# PiDGC.net
KiCad netlist of a schematic drawn in EAGLE
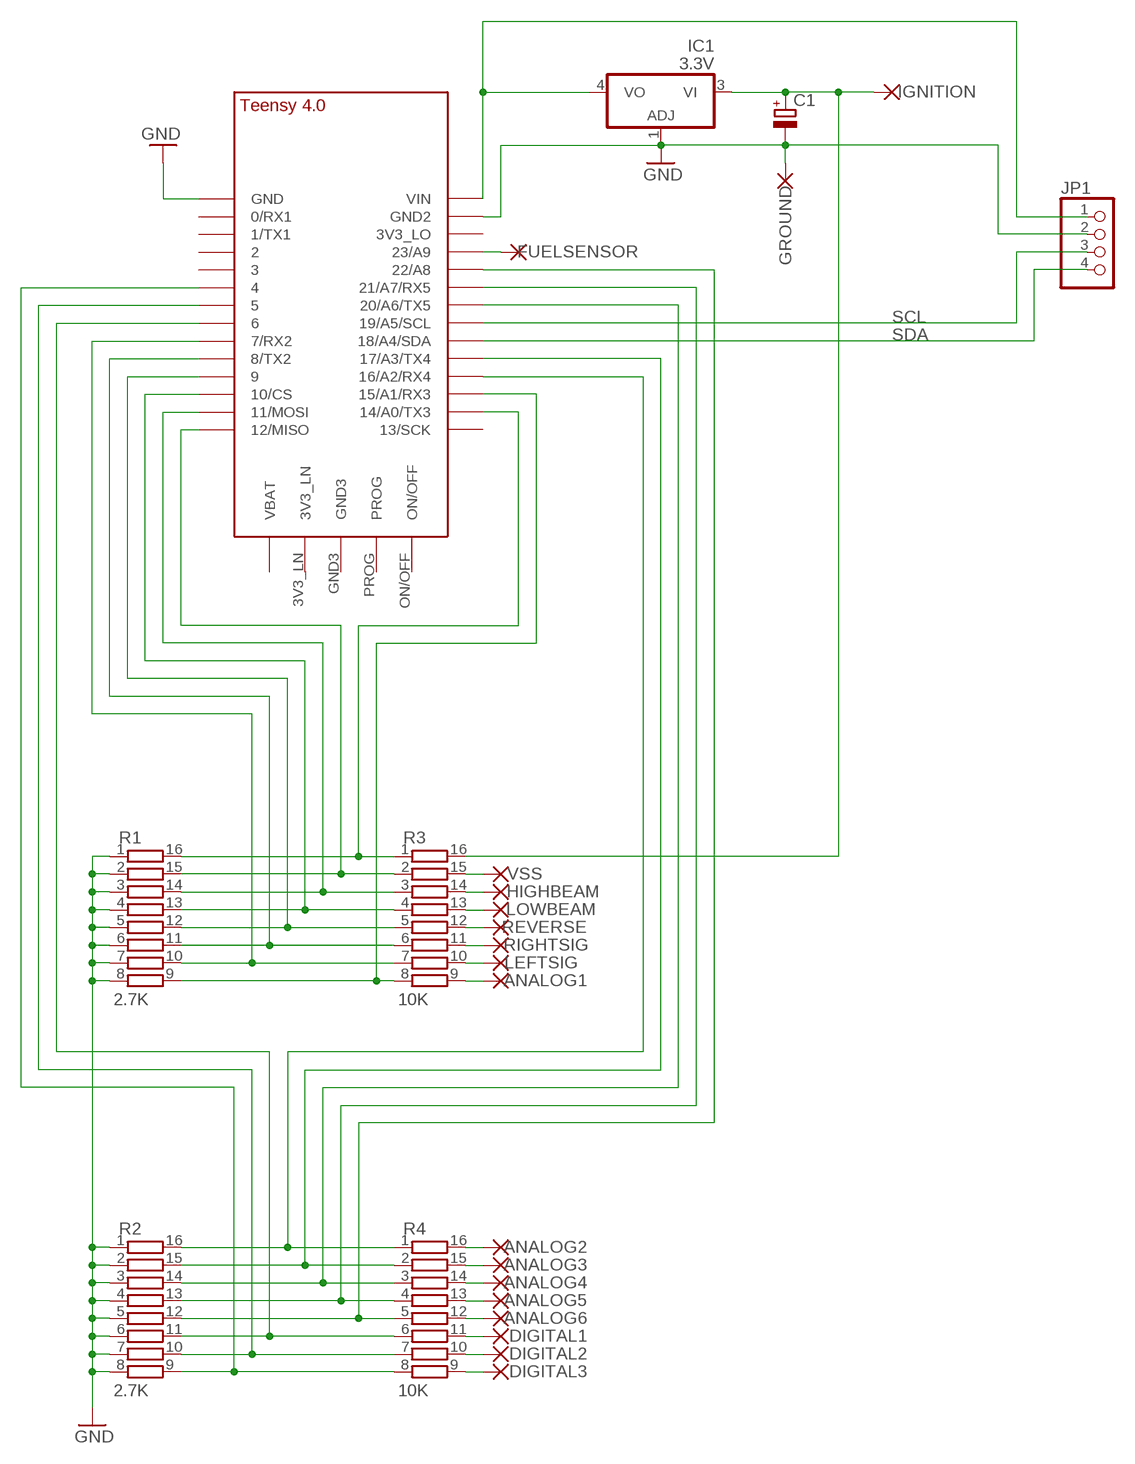
[diagram p0: schematic, sheet 1]

(export (version "E")
  (design (tool "Eeschema 10.0.6"))
  (components
    (comp (ref "ANALOG1")
      (value "WIREPAD3,81/1,4")
      (footprint "eagle-import:3,81_1,4")
      (libsource (lib "eagle-import") (part "WIREPAD3,81/1,4"))
    )
    (comp (ref "ANALOG2")
      (value "WIREPAD3,81/1,4")
      (footprint "eagle-import:3,81_1,4")
      (libsource (lib "eagle-import") (part "WIREPAD3,81/1,4"))
    )
    (comp (ref "ANALOG3")
      (value "WIREPAD3,81/1,4")
      (footprint "eagle-import:3,81_1,4")
      (libsource (lib "eagle-import") (part "WIREPAD3,81/1,4"))
    )
    (comp (ref "ANALOG4")
      (value "WIREPAD3,81/1,4")
      (footprint "eagle-import:3,81_1,4")
      (libsource (lib "eagle-import") (part "WIREPAD3,81/1,4"))
    )
    (comp (ref "ANALOG5")
      (value "WIREPAD3,81/1,4")
      (footprint "eagle-import:3,81_1,4")
      (libsource (lib "eagle-import") (part "WIREPAD3,81/1,4"))
    )
    (comp (ref "ANALOG6")
      (value "WIREPAD3,81/1,4")
      (footprint "eagle-import:3,81_1,4")
      (libsource (lib "eagle-import") (part "WIREPAD3,81/1,4"))
    )
    (comp (ref "C1")
      (value "CPOL-EUE7.5-16")
      (footprint "eagle-import:E7,5-16")
      (libsource (lib "eagle-import") (part "CPOL-EUE7.5-16"))
    )
    (comp (ref "DIGITAL1")
      (value "WIREPAD3,81/1,4")
      (footprint "eagle-import:3,81_1,4")
      (libsource (lib "eagle-import") (part "WIREPAD3,81/1,4"))
    )
    (comp (ref "DIGITAL2")
      (value "WIREPAD3,81/1,4")
      (footprint "eagle-import:3,81_1,4")
      (libsource (lib "eagle-import") (part "WIREPAD3,81/1,4"))
    )
    (comp (ref "DIGITAL3")
      (value "WIREPAD3,81/1,4")
      (footprint "eagle-import:3,81_1,4")
      (libsource (lib "eagle-import") (part "WIREPAD3,81/1,4"))
    )
    (comp (ref "FUELSENSOR")
      (value "WIREPAD3,81/1,4")
      (footprint "eagle-import:3,81_1,4")
      (libsource (lib "eagle-import") (part "WIREPAD3,81/1,4"))
    )
    (comp (ref "GROUND")
      (value "WIREPAD3,81/1,4")
      (footprint "eagle-import:3,81_1,4")
      (libsource (lib "eagle-import") (part "WIREPAD3,81/1,4"))
    )
    (comp (ref "HIGHBEAM")
      (value "WIREPAD3,81/1,4")
      (footprint "eagle-import:3,81_1,4")
      (libsource (lib "eagle-import") (part "WIREPAD3,81/1,4"))
    )
    (comp (ref "IC1")
      (value "3.3V")
      (footprint "eagle-import:SOT223")
      (libsource (lib "eagle-import") (part "317EMP"))
    )
    (comp (ref "IGNITION")
      (value "WIREPAD3,81/1,4")
      (footprint "eagle-import:3,81_1,4")
      (libsource (lib "eagle-import") (part "WIREPAD3,81/1,4"))
    )
    (comp (ref "JP1")
      (value "PINHD-1X4")
      (footprint "eagle-import:1X04")
      (libsource (lib "eagle-import") (part "PINHD-1X4"))
    )
    (comp (ref "LEFTSIG")
      (value "WIREPAD3,81/1,4")
      (footprint "eagle-import:3,81_1,4")
      (libsource (lib "eagle-import") (part "WIREPAD3,81/1,4"))
    )
    (comp (ref "LOWBEAM")
      (value "WIREPAD3,81/1,4")
      (footprint "eagle-import:3,81_1,4")
      (libsource (lib "eagle-import") (part "WIREPAD3,81/1,4"))
    )
    (comp (ref "R1")
      (value "2.7K")
      (footprint "eagle-import:SO16")
      (libsource (lib "eagle-import") (part "2NBS16-8"))
    )
    (comp (ref "R2")
      (value "2.7K")
      (footprint "eagle-import:SO16")
      (libsource (lib "eagle-import") (part "2NBS16-8"))
    )
    (comp (ref "R3")
      (value "10K")
      (footprint "eagle-import:SO16")
      (libsource (lib "eagle-import") (part "2NBS16-8"))
    )
    (comp (ref "R4")
      (value "10K")
      (footprint "eagle-import:SO16")
      (libsource (lib "eagle-import") (part "2NBS16-8"))
    )
    (comp (ref "REVERSE")
      (value "WIREPAD3,81/1,4")
      (footprint "eagle-import:3,81_1,4")
      (libsource (lib "eagle-import") (part "WIREPAD3,81/1,4"))
    )
    (comp (ref "RIGHTSIG")
      (value "WIREPAD3,81/1,4")
      (footprint "eagle-import:3,81_1,4")
      (libsource (lib "eagle-import") (part "WIREPAD3,81/1,4"))
    )
    (comp (ref "U$1")
      (value "TEENSY_4.0")
      (footprint "eagle-import:TEENSY_4.0")
      (libsource (lib "eagle-import") (part "TEENSY_4.0"))
    )
    (comp (ref "VSS")
      (value "WIREPAD3,81/1,4")
      (footprint "eagle-import:3,81_1,4")
      (libsource (lib "eagle-import") (part "WIREPAD3,81/1,4"))
    )
  )
  (nets
    (net (code "1") (name "/SCL") (class "Default")
      (node (ref "JP1") (pin "3") (pinfunction "3_3") (pintype "passive"))
      (node (ref "U$1") (pin "19/A5/SCL") (pinfunction "19/A5/SCL_19/A5/SCL") (pintype "bidirectional"))
    )
    (net (code "2") (name "/SDA") (class "Default")
      (node (ref "JP1") (pin "4") (pinfunction "4_4") (pintype "passive"))
      (node (ref "U$1") (pin "18/A4/SDA") (pinfunction "18/A4/SDA_18/A4/SDA") (pintype "bidirectional"))
    )
    (net (code "3") (name "GND") (class "Default")
      (node (ref "C1") (pin "-") (pinfunction "-_-") (pintype "passive"))
      (node (ref "GROUND") (pin "1") (pinfunction "P_1") (pintype "passive"))
      (node (ref "IC1") (pin "1") (pinfunction "ADJ_1") (pintype "input"))
      (node (ref "JP1") (pin "2") (pinfunction "2_2") (pintype "passive"))
      (node (ref "R1") (pin "1") (pinfunction "1_1") (pintype "passive"))
      (node (ref "R1") (pin "2") (pinfunction "2_2") (pintype "passive"))
      (node (ref "R1") (pin "3") (pinfunction "3_3") (pintype "passive"))
      (node (ref "R1") (pin "4") (pinfunction "4_4") (pintype "passive"))
      (node (ref "R1") (pin "5") (pinfunction "5_5") (pintype "passive"))
      (node (ref "R1") (pin "6") (pinfunction "6_6") (pintype "passive"))
      (node (ref "R1") (pin "7") (pinfunction "7_7") (pintype "passive"))
      (node (ref "R1") (pin "8") (pinfunction "8_8") (pintype "passive"))
      (node (ref "R2") (pin "1") (pinfunction "1_1") (pintype "passive"))
      (node (ref "R2") (pin "2") (pinfunction "2_2") (pintype "passive"))
      (node (ref "R2") (pin "3") (pinfunction "3_3") (pintype "passive"))
      (node (ref "R2") (pin "4") (pinfunction "4_4") (pintype "passive"))
      (node (ref "R2") (pin "5") (pinfunction "5_5") (pintype "passive"))
      (node (ref "R2") (pin "6") (pinfunction "6_6") (pintype "passive"))
      (node (ref "R2") (pin "7") (pinfunction "7_7") (pintype "passive"))
      (node (ref "R2") (pin "8") (pinfunction "8_8") (pintype "passive"))
      (node (ref "U$1") (pin "GND") (pinfunction "GND_GND") (pintype "bidirectional"))
      (node (ref "U$1") (pin "GND2") (pinfunction "GND2_GND2") (pintype "bidirectional"))
    )
    (net (code "4") (name "Net-(ANALOG1-P)") (class "Default")
      (node (ref "ANALOG1") (pin "1") (pinfunction "P_1") (pintype "passive"))
      (node (ref "R3") (pin "9") (pinfunction "9_9") (pintype "passive"))
    )
    (net (code "5") (name "Net-(ANALOG2-P)") (class "Default")
      (node (ref "ANALOG2") (pin "1") (pinfunction "P_1") (pintype "passive"))
      (node (ref "R4") (pin "16") (pinfunction "16_16") (pintype "passive"))
    )
    (net (code "6") (name "Net-(ANALOG3-P)") (class "Default")
      (node (ref "ANALOG3") (pin "1") (pinfunction "P_1") (pintype "passive"))
      (node (ref "R4") (pin "15") (pinfunction "15_15") (pintype "passive"))
    )
    (net (code "7") (name "Net-(ANALOG4-P)") (class "Default")
      (node (ref "ANALOG4") (pin "1") (pinfunction "P_1") (pintype "passive"))
      (node (ref "R4") (pin "14") (pinfunction "14_14") (pintype "passive"))
    )
    (net (code "8") (name "Net-(ANALOG5-P)") (class "Default")
      (node (ref "ANALOG5") (pin "1") (pinfunction "P_1") (pintype "passive"))
      (node (ref "R4") (pin "13") (pinfunction "13_13") (pintype "passive"))
    )
    (net (code "9") (name "Net-(ANALOG6-P)") (class "Default")
      (node (ref "ANALOG6") (pin "1") (pinfunction "P_1") (pintype "passive"))
      (node (ref "R4") (pin "12") (pinfunction "12_12") (pintype "passive"))
    )
    (net (code "10") (name "Net-(DIGITAL1-P)") (class "Default")
      (node (ref "DIGITAL1") (pin "1") (pinfunction "P_1") (pintype "passive"))
      (node (ref "R4") (pin "11") (pinfunction "11_11") (pintype "passive"))
    )
    (net (code "11") (name "Net-(DIGITAL2-P)") (class "Default")
      (node (ref "DIGITAL2") (pin "1") (pinfunction "P_1") (pintype "passive"))
      (node (ref "R4") (pin "10") (pinfunction "10_10") (pintype "passive"))
    )
    (net (code "12") (name "Net-(DIGITAL3-P)") (class "Default")
      (node (ref "DIGITAL3") (pin "1") (pinfunction "P_1") (pintype "passive"))
      (node (ref "R4") (pin "9") (pinfunction "9_9") (pintype "passive"))
    )
    (net (code "13") (name "Net-(FUELSENSOR-P)") (class "Default")
      (node (ref "FUELSENSOR") (pin "1") (pinfunction "P_1") (pintype "passive"))
      (node (ref "U$1") (pin "23/A9") (pinfunction "23/A9_23/A9") (pintype "bidirectional"))
    )
    (net (code "14") (name "Net-(HIGHBEAM-P)") (class "Default")
      (node (ref "HIGHBEAM") (pin "1") (pinfunction "P_1") (pintype "passive"))
      (node (ref "R3") (pin "14") (pinfunction "14_14") (pintype "passive"))
    )
    (net (code "15") (name "Net-(IC1-VI)") (class "Default")
      (node (ref "C1") (pin "+") (pinfunction "+_+") (pintype "passive"))
      (node (ref "IC1") (pin "3") (pinfunction "VI_3") (pintype "input"))
      (node (ref "IGNITION") (pin "1") (pinfunction "P_1") (pintype "passive"))
      (node (ref "R3") (pin "16") (pinfunction "16_16") (pintype "passive"))
    )
    (net (code "16") (name "Net-(IC1-VO)") (class "Default")
      (node (ref "IC1") (pin "4") (pinfunction "VO_4") (pintype "passive"))
      (node (ref "JP1") (pin "1") (pinfunction "1_1") (pintype "passive"))
      (node (ref "U$1") (pin "VIN") (pinfunction "VIN_VIN") (pintype "bidirectional"))
    )
    (net (code "17") (name "Net-(LEFTSIG-P)") (class "Default")
      (node (ref "LEFTSIG") (pin "1") (pinfunction "P_1") (pintype "passive"))
      (node (ref "R3") (pin "10") (pinfunction "10_10") (pintype "passive"))
    )
    (net (code "18") (name "Net-(LOWBEAM-P)") (class "Default")
      (node (ref "LOWBEAM") (pin "1") (pinfunction "P_1") (pintype "passive"))
      (node (ref "R3") (pin "13") (pinfunction "13_13") (pintype "passive"))
    )
    (net (code "19") (name "Net-(R1-Pad13)") (class "Default")
      (node (ref "R1") (pin "13") (pinfunction "13_13") (pintype "passive"))
      (node (ref "R3") (pin "4") (pinfunction "4_4") (pintype "passive"))
      (node (ref "U$1") (pin "10/CS") (pinfunction "10/CS_10/CS") (pintype "bidirectional"))
    )
    (net (code "20") (name "Net-(R1-Pad14)") (class "Default")
      (node (ref "R1") (pin "14") (pinfunction "14_14") (pintype "passive"))
      (node (ref "R3") (pin "3") (pinfunction "3_3") (pintype "passive"))
      (node (ref "U$1") (pin "11/MOSI") (pinfunction "11/MOSI_11/MOSI") (pintype "bidirectional"))
    )
    (net (code "21") (name "Net-(R1-Pad15)") (class "Default")
      (node (ref "R1") (pin "15") (pinfunction "15_15") (pintype "passive"))
      (node (ref "R3") (pin "2") (pinfunction "2_2") (pintype "passive"))
      (node (ref "U$1") (pin "12/MISO") (pinfunction "12/MISO_12/MISO") (pintype "bidirectional"))
    )
    (net (code "22") (name "Net-(R2-Pad10)") (class "Default")
      (node (ref "R2") (pin "10") (pinfunction "10_10") (pintype "passive"))
      (node (ref "R4") (pin "7") (pinfunction "7_7") (pintype "passive"))
      (node (ref "U$1") (pin "5") (pinfunction "5_5") (pintype "bidirectional"))
    )
    (net (code "23") (name "Net-(R2-Pad11)") (class "Default")
      (node (ref "R2") (pin "11") (pinfunction "11_11") (pintype "passive"))
      (node (ref "R4") (pin "6") (pinfunction "6_6") (pintype "passive"))
      (node (ref "U$1") (pin "6") (pinfunction "6_6") (pintype "bidirectional"))
    )
    (net (code "24") (name "Net-(R2-Pad12)") (class "Default")
      (node (ref "R2") (pin "12") (pinfunction "12_12") (pintype "passive"))
      (node (ref "R4") (pin "5") (pinfunction "5_5") (pintype "passive"))
      (node (ref "U$1") (pin "22/A8") (pinfunction "22/A8_22/A8") (pintype "bidirectional"))
    )
    (net (code "25") (name "Net-(REVERSE-P)") (class "Default")
      (node (ref "R3") (pin "12") (pinfunction "12_12") (pintype "passive"))
      (node (ref "REVERSE") (pin "1") (pinfunction "P_1") (pintype "passive"))
    )
    (net (code "26") (name "Net-(RIGHTSIG-P)") (class "Default")
      (node (ref "R3") (pin "11") (pinfunction "11_11") (pintype "passive"))
      (node (ref "RIGHTSIG") (pin "1") (pinfunction "P_1") (pintype "passive"))
    )
    (net (code "27") (name "Net-(U$1-4)") (class "Default")
      (node (ref "R2") (pin "9") (pinfunction "9_9") (pintype "passive"))
      (node (ref "R4") (pin "8") (pinfunction "8_8") (pintype "passive"))
      (node (ref "U$1") (pin "4/CANRX") (pinfunction "4_4/CANRX") (pintype "bidirectional"))
    )
    (net (code "28") (name "Net-(U$1-7{slash}RX2)") (class "Default")
      (node (ref "R1") (pin "10") (pinfunction "10_10") (pintype "passive"))
      (node (ref "R3") (pin "7") (pinfunction "7_7") (pintype "passive"))
      (node (ref "U$1") (pin "7") (pinfunction "7/RX2_7") (pintype "bidirectional"))
    )
    (net (code "29") (name "Net-(U$1-8{slash}TX2)") (class "Default")
      (node (ref "R1") (pin "11") (pinfunction "11_11") (pintype "passive"))
      (node (ref "R3") (pin "6") (pinfunction "6_6") (pintype "passive"))
      (node (ref "U$1") (pin "8") (pinfunction "8/TX2_8") (pintype "bidirectional"))
    )
    (net (code "30") (name "Net-(U$1-9)") (class "Default")
      (node (ref "R1") (pin "12") (pinfunction "12_12") (pintype "passive"))
      (node (ref "R3") (pin "5") (pinfunction "5_5") (pintype "passive"))
      (node (ref "U$1") (pin "9/CS") (pinfunction "9_9/CS") (pintype "bidirectional"))
    )
    (net (code "31") (name "Net-(U$1-14{slash}A0{slash}TX3)") (class "Default")
      (node (ref "R1") (pin "16") (pinfunction "16_16") (pintype "passive"))
      (node (ref "R3") (pin "1") (pinfunction "1_1") (pintype "passive"))
      (node (ref "U$1") (pin "14/A0") (pinfunction "14/A0/TX3_14/A0") (pintype "bidirectional"))
    )
    (net (code "32") (name "Net-(U$1-15{slash}A1{slash}RX3)") (class "Default")
      (node (ref "R1") (pin "9") (pinfunction "9_9") (pintype "passive"))
      (node (ref "R3") (pin "8") (pinfunction "8_8") (pintype "passive"))
      (node (ref "U$1") (pin "15/A1") (pinfunction "15/A1/RX3_15/A1") (pintype "bidirectional"))
    )
    (net (code "33") (name "Net-(U$1-16{slash}A2{slash}RX4)") (class "Default")
      (node (ref "R2") (pin "16") (pinfunction "16_16") (pintype "passive"))
      (node (ref "R4") (pin "1") (pinfunction "1_1") (pintype "passive"))
      (node (ref "U$1") (pin "16/A2") (pinfunction "16/A2/RX4_16/A2") (pintype "bidirectional"))
    )
    (net (code "34") (name "Net-(U$1-17{slash}A3{slash}TX4)") (class "Default")
      (node (ref "R2") (pin "15") (pinfunction "15_15") (pintype "passive"))
      (node (ref "R4") (pin "2") (pinfunction "2_2") (pintype "passive"))
      (node (ref "U$1") (pin "17/A3") (pinfunction "17/A3/TX4_17/A3") (pintype "bidirectional"))
    )
    (net (code "35") (name "Net-(U$1-20{slash}A6{slash}TX5)") (class "Default")
      (node (ref "R2") (pin "14") (pinfunction "14_14") (pintype "passive"))
      (node (ref "R4") (pin "3") (pinfunction "3_3") (pintype "passive"))
      (node (ref "U$1") (pin "20/A6") (pinfunction "20/A6/TX5_20/A6") (pintype "bidirectional"))
    )
    (net (code "36") (name "Net-(U$1-21{slash}A7{slash}RX5)") (class "Default")
      (node (ref "R2") (pin "13") (pinfunction "13_13") (pintype "passive"))
      (node (ref "R4") (pin "4") (pinfunction "4_4") (pintype "passive"))
      (node (ref "U$1") (pin "21/A7") (pinfunction "21/A7/RX5_21/A7") (pintype "bidirectional"))
    )
    (net (code "37") (name "Net-(VSS-P)") (class "Default")
      (node (ref "R3") (pin "15") (pinfunction "15_15") (pintype "passive"))
      (node (ref "VSS") (pin "1") (pinfunction "P_1") (pintype "passive"))
    )
    (net (code "38") (name "unconnected-(U$1-0{slash}RX1-Pad0{slash}RX)") (class "Default")
      (node (ref "U$1") (pin "0/RX") (pinfunction "0/RX1_0/RX") (pintype "bidirectional"))
    )
    (net (code "39") (name "unconnected-(U$1-1{slash}TX1-Pad1{slash}TX)") (class "Default")
      (node (ref "U$1") (pin "1/TX") (pinfunction "1/TX1_1/TX") (pintype "bidirectional"))
    )
    (net (code "40") (name "unconnected-(U$1-3-Pad3{slash}CANTX)") (class "Default")
      (node (ref "U$1") (pin "3/CANTX") (pinfunction "3_3/CANTX") (pintype "bidirectional"))
    )
    (net (code "41") (name "unconnected-(U$1-Pad2)") (class "Default")
      (node (ref "U$1") (pin "2") (pinfunction "2_2") (pintype "bidirectional"))
    )
    (net (code "42") (name "unconnected-(U$1-Pad3V3_LN)") (class "Default")
      (node (ref "U$1") (pin "3V3_LN") (pinfunction "3V3_LN_3V3_LN") (pintype "bidirectional"))
    )
    (net (code "43") (name "unconnected-(U$1-Pad3V3_LO)") (class "Default")
      (node (ref "U$1") (pin "3V3_LO") (pinfunction "3V3_LO_3V3_LO") (pintype "bidirectional"))
    )
    (net (code "44") (name "unconnected-(U$1-Pad13{slash}SCK)") (class "Default")
      (node (ref "U$1") (pin "13/SCK") (pinfunction "13/SCK_13/SCK") (pintype "bidirectional"))
    )
    (net (code "45") (name "unconnected-(U$1-PadGND3)") (class "Default")
      (node (ref "U$1") (pin "GND3") (pinfunction "GND3_GND3") (pintype "bidirectional"))
    )
    (net (code "46") (name "unconnected-(U$1-PadON{slash}OFF)") (class "Default")
      (node (ref "U$1") (pin "ON/OFF") (pinfunction "ON/OFF_ON/OFF") (pintype "bidirectional"))
    )
    (net (code "47") (name "unconnected-(U$1-PadPROG)") (class "Default")
      (node (ref "U$1") (pin "PROG") (pinfunction "PROG_PROG") (pintype "bidirectional"))
    )
    (net (code "48") (name "unconnected-(U$1-VBAT-PadVBAT\\)") (class "Default")
      (node (ref "U$1") (pin "VBAT\\") (pinfunction "VBAT_VBAT\\") (pintype "bidirectional"))
    )
  )
)
